# Interface.net
KiCad netlist of a schematic drawn in Altium Designer
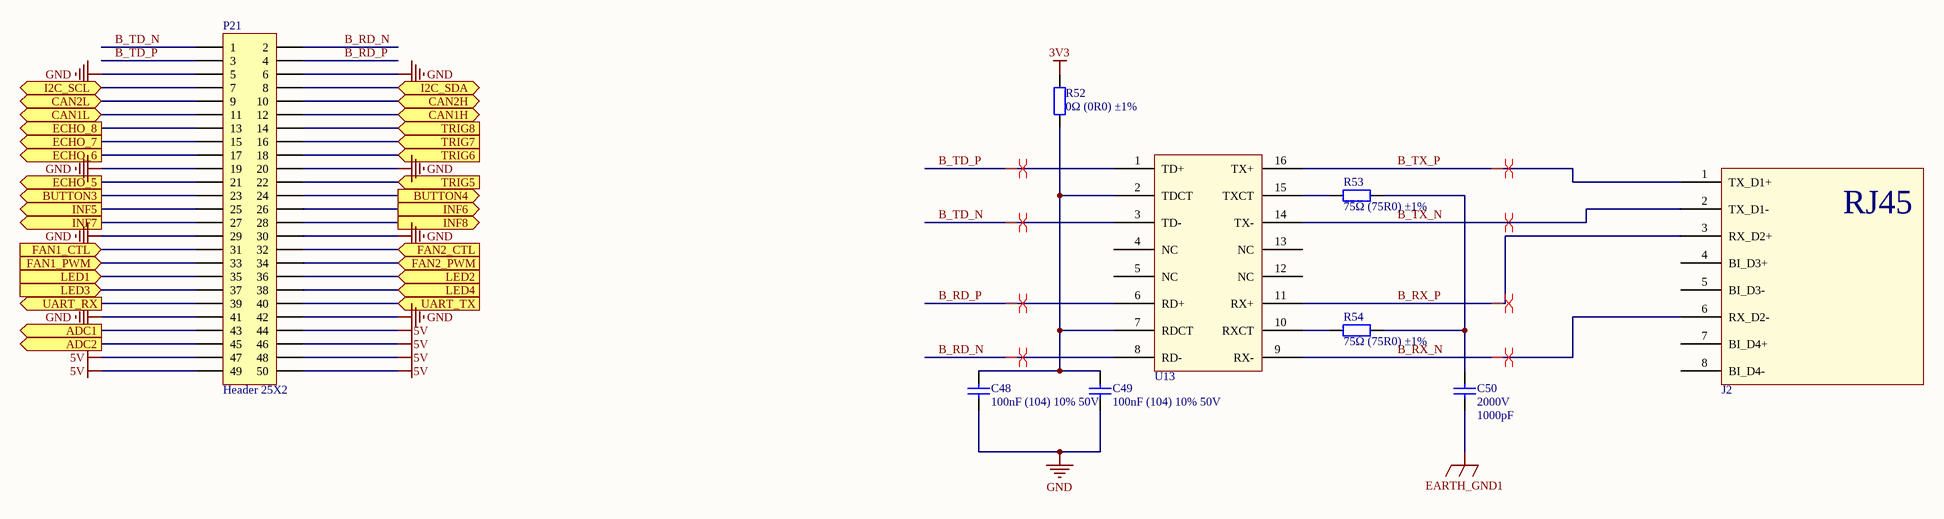
[diagram p0: Interface.SchDoc]

(export (version "E")
  (design (tool "Eeschema 10.0.6"))
  (components
    (comp (ref "C48")
      (value "100nF (104) 10% 50V")
      (footprint "0603_C")
      (description "贴片电容")
      (libsource (lib "Miscellaneous Devices LC") (part "0603 100nF (104) 10% 50V"))
    )
    (comp (ref "C49")
      (value "100nF (104) 10% 50V")
      (footprint "0603_C")
      (description "贴片电容")
      (libsource (lib "Miscellaneous Devices LC") (part "0603 100nF (104) 10% 50V"))
    )
    (comp (ref "C50")
      (value "2000V")
      (footprint "CAP1210N")
      (description "CAP 1000pF ±10% 2000V (2kV) Ceramic Capacitor X7R 1210 (3225 Metric)")
      (fields
        (field (name "ALTIUM_VALUE") "1000pF")
        (field (name "MANUFACTURER") "Samsung Electro-Mechanics")
        (field (name "MANUFACTURER PART NUMBER") "CL32B102KJFNNNE")
      )
      (libsource (lib "RoboteX") (part "Cap Non-Polar"))
    )
    (comp (ref "J2")
      (value "Jack Modular Connector 8p8c (RJ45, Ethernet) Vertical Unshielded Cat3")
      (footprint "RJ45-5556416-1")
      (description "RJ45 connector 180 degrees")
      (fields (field (name "PART NUMBER") "5556416-1") (field (name "MANUFACTURER") "TE"))
      (libsource (lib "RoboteX") (part "RJ45_180"))
    )
    (comp (ref "P21")
      (value "Header 25X2")
      (footprint "HDR_2X25")
      (description "Header, 25-Pin, Dual row")
      (fields (field (name "PUBLISHER") "Altium Limited"))
      (libsource (lib "Miscellaneous Connectors") (part "Header 25X2"))
    )
    (comp (ref "R52")
      (value "0Ω (0R0) ±1%")
      (footprint "0603_R")
      (description "贴片电阻")
      (libsource (lib "Miscellaneous Devices LC") (part "0603 0Ω (0R0) 1%"))
    )
    (comp (ref "R53")
      (value "75Ω (75R0) ±1%")
      (footprint "0603_R")
      (description "贴片电阻")
      (libsource (lib "Miscellaneous Devices LC") (part "0603 75Ω (75R0) 1%"))
    )
    (comp (ref "R54")
      (value "75Ω (75R0) ±1%")
      (footprint "0603_R")
      (description "贴片电阻")
      (libsource (lib "Miscellaneous Devices LC") (part "0603 75Ω (75R0) 1%"))
    )
    (comp (ref "U13")
      (value "TRANSFORMER")
      (footprint "Bel_transformer")
      (description "MODULE XFRMR LAN 10/100B-TX SMD")
      (fields
        (field (name "MANUFACTURER") "Bel Fuse Inc.")
        (field (name "MANUFACTURER PART NUMBER") "S558-5999-U7-F")
      )
      (libsource (lib "RoboteX") (part "Transformer"))
    )
  )
  (nets
    (net (code "1") (name "/ADC1") (class "Default")
      (node (ref "P21") (pin "43") (pinfunction "43_43") (pintype "passive"))
    )
    (net (code "2") (name "/ADC2") (class "Default")
      (node (ref "P21") (pin "45") (pinfunction "45_45") (pintype "passive"))
    )
    (net (code "3") (name "/BUTTON3") (class "Default")
      (node (ref "P21") (pin "23") (pinfunction "23_23") (pintype "passive"))
    )
    (net (code "4") (name "/BUTTON4") (class "Default")
      (node (ref "P21") (pin "24") (pinfunction "24_24") (pintype "passive"))
    )
    (net (code "5") (name "/B_RD_N") (class "Default")
      (node (ref "P21") (pin "2") (pinfunction "2_2") (pintype "passive"))
      (node (ref "U13") (pin "8") (pinfunction "RD-_8") (pintype "passive"))
    )
    (net (code "6") (name "/B_RD_P") (class "Default")
      (node (ref "P21") (pin "4") (pinfunction "4_4") (pintype "passive"))
      (node (ref "U13") (pin "6") (pinfunction "RD+_6") (pintype "passive"))
    )
    (net (code "7") (name "/B_RX_N") (class "Default")
      (node (ref "J2") (pin "6") (pinfunction "RX_D2-_6") (pintype "passive"))
      (node (ref "U13") (pin "9") (pinfunction "RX-_9") (pintype "passive"))
    )
    (net (code "8") (name "/B_RX_P") (class "Default")
      (node (ref "J2") (pin "3") (pinfunction "RX_D2+_3") (pintype "passive"))
      (node (ref "U13") (pin "11") (pinfunction "RX+_11") (pintype "passive"))
    )
    (net (code "9") (name "/B_TD_N") (class "Default")
      (node (ref "P21") (pin "1") (pinfunction "1_1") (pintype "passive"))
      (node (ref "U13") (pin "3") (pinfunction "TD-_3") (pintype "passive"))
    )
    (net (code "10") (name "/B_TD_P") (class "Default")
      (node (ref "P21") (pin "3") (pinfunction "3_3") (pintype "passive"))
      (node (ref "U13") (pin "1") (pinfunction "TD+_1") (pintype "passive"))
    )
    (net (code "11") (name "/B_TX_N") (class "Default")
      (node (ref "J2") (pin "2") (pinfunction "TX_D1-_2") (pintype "passive"))
      (node (ref "U13") (pin "14") (pinfunction "TX-_14") (pintype "passive"))
    )
    (net (code "12") (name "/B_TX_P") (class "Default")
      (node (ref "J2") (pin "1") (pinfunction "TX_D1+_1") (pintype "passive"))
      (node (ref "U13") (pin "16") (pinfunction "TX+_16") (pintype "passive"))
    )
    (net (code "13") (name "/CAN1H") (class "Default")
      (node (ref "P21") (pin "12") (pinfunction "12_12") (pintype "passive"))
    )
    (net (code "14") (name "/CAN1L") (class "Default")
      (node (ref "P21") (pin "11") (pinfunction "11_11") (pintype "passive"))
    )
    (net (code "15") (name "/CAN2H") (class "Default")
      (node (ref "P21") (pin "10") (pinfunction "10_10") (pintype "passive"))
    )
    (net (code "16") (name "/CAN2L") (class "Default")
      (node (ref "P21") (pin "9") (pinfunction "9_9") (pintype "passive"))
    )
    (net (code "17") (name "/ECHO_5") (class "Default")
      (node (ref "P21") (pin "21") (pinfunction "21_21") (pintype "passive"))
    )
    (net (code "18") (name "/ECHO_6") (class "Default")
      (node (ref "P21") (pin "17") (pinfunction "17_17") (pintype "passive"))
    )
    (net (code "19") (name "/ECHO_7") (class "Default")
      (node (ref "P21") (pin "15") (pinfunction "15_15") (pintype "passive"))
    )
    (net (code "20") (name "/ECHO_8") (class "Default")
      (node (ref "P21") (pin "13") (pinfunction "13_13") (pintype "passive"))
    )
    (net (code "21") (name "/FAN1_CTL") (class "Default")
      (node (ref "P21") (pin "31") (pinfunction "31_31") (pintype "passive"))
    )
    (net (code "22") (name "/FAN1_PWM") (class "Default")
      (node (ref "P21") (pin "33") (pinfunction "33_33") (pintype "passive"))
    )
    (net (code "23") (name "/FAN2_CTL") (class "Default")
      (node (ref "P21") (pin "32") (pinfunction "32_32") (pintype "passive"))
    )
    (net (code "24") (name "/FAN2_PWM") (class "Default")
      (node (ref "P21") (pin "34") (pinfunction "34_34") (pintype "passive"))
    )
    (net (code "25") (name "/I2C_SCL") (class "Default")
      (node (ref "P21") (pin "7") (pinfunction "7_7") (pintype "passive"))
    )
    (net (code "26") (name "/I2C_SDA") (class "Default")
      (node (ref "P21") (pin "8") (pinfunction "8_8") (pintype "passive"))
    )
    (net (code "27") (name "/INF5") (class "Default")
      (node (ref "P21") (pin "25") (pinfunction "25_25") (pintype "passive"))
    )
    (net (code "28") (name "/INF6") (class "Default")
      (node (ref "P21") (pin "26") (pinfunction "26_26") (pintype "passive"))
    )
    (net (code "29") (name "/INF7") (class "Default")
      (node (ref "P21") (pin "27") (pinfunction "27_27") (pintype "passive"))
    )
    (net (code "30") (name "/INF8") (class "Default")
      (node (ref "P21") (pin "28") (pinfunction "28_28") (pintype "passive"))
    )
    (net (code "31") (name "/LED1") (class "Default")
      (node (ref "P21") (pin "35") (pinfunction "35_35") (pintype "passive"))
    )
    (net (code "32") (name "/LED2") (class "Default")
      (node (ref "P21") (pin "36") (pinfunction "36_36") (pintype "passive"))
    )
    (net (code "33") (name "/LED3") (class "Default")
      (node (ref "P21") (pin "37") (pinfunction "37_37") (pintype "passive"))
    )
    (net (code "34") (name "/LED4") (class "Default")
      (node (ref "P21") (pin "38") (pinfunction "38_38") (pintype "passive"))
    )
    (net (code "35") (name "/TRIG5") (class "Default")
      (node (ref "P21") (pin "22") (pinfunction "22_22") (pintype "passive"))
    )
    (net (code "36") (name "/TRIG6") (class "Default")
      (node (ref "P21") (pin "18") (pinfunction "18_18") (pintype "passive"))
    )
    (net (code "37") (name "/TRIG7") (class "Default")
      (node (ref "P21") (pin "16") (pinfunction "16_16") (pintype "passive"))
    )
    (net (code "38") (name "/TRIG8") (class "Default")
      (node (ref "P21") (pin "14") (pinfunction "14_14") (pintype "passive"))
    )
    (net (code "39") (name "/UART_RX") (class "Default")
      (node (ref "P21") (pin "39") (pinfunction "39_39") (pintype "passive"))
    )
    (net (code "40") (name "/UART_TX") (class "Default")
      (node (ref "P21") (pin "40") (pinfunction "40_40") (pintype "passive"))
    )
    (net (code "41") (name "3V3") (class "Default")
      (node (ref "R52") (pin "2") (pinfunction "2_2") (pintype "passive"))
    )
    (net (code "42") (name "5V") (class "Default")
      (node (ref "P21") (pin "44") (pinfunction "44_44") (pintype "passive"))
      (node (ref "P21") (pin "46") (pinfunction "46_46") (pintype "passive"))
      (node (ref "P21") (pin "47") (pinfunction "47_47") (pintype "passive"))
      (node (ref "P21") (pin "48") (pinfunction "48_48") (pintype "passive"))
      (node (ref "P21") (pin "49") (pinfunction "49_49") (pintype "passive"))
      (node (ref "P21") (pin "50") (pinfunction "50_50") (pintype "passive"))
    )
    (net (code "43") (name "EARTH_GND1") (class "Default")
      (node (ref "C50") (pin "1") (pinfunction "1_1") (pintype "passive"))
    )
    (net (code "44") (name "GND") (class "Default")
      (node (ref "C48") (pin "2") (pinfunction "2_2") (pintype "passive"))
      (node (ref "C49") (pin "1") (pinfunction "1_1") (pintype "passive"))
      (node (ref "P21") (pin "19") (pinfunction "19_19") (pintype "passive"))
      (node (ref "P21") (pin "20") (pinfunction "20_20") (pintype "passive"))
      (node (ref "P21") (pin "29") (pinfunction "29_29") (pintype "passive"))
      (node (ref "P21") (pin "30") (pinfunction "30_30") (pintype "passive"))
      (node (ref "P21") (pin "41") (pinfunction "41_41") (pintype "passive"))
      (node (ref "P21") (pin "42") (pinfunction "42_42") (pintype "passive"))
      (node (ref "P21") (pin "5") (pinfunction "5_5") (pintype "passive"))
      (node (ref "P21") (pin "6") (pinfunction "6_6") (pintype "passive"))
    )
    (net (code "45") (name "Net-(C50-Pad2)") (class "Default")
      (node (ref "C50") (pin "2") (pinfunction "2_2") (pintype "passive"))
      (node (ref "R53") (pin "2") (pinfunction "2_2") (pintype "passive"))
      (node (ref "R54") (pin "2") (pinfunction "2_2") (pintype "passive"))
    )
    (net (code "46") (name "Net-(U13-RDCT)") (class "Default")
      (node (ref "C48") (pin "1") (pinfunction "1_1") (pintype "passive"))
      (node (ref "C49") (pin "2") (pinfunction "2_2") (pintype "passive"))
      (node (ref "R52") (pin "1") (pinfunction "1_1") (pintype "passive"))
      (node (ref "U13") (pin "2") (pinfunction "TDCT_2") (pintype "passive"))
      (node (ref "U13") (pin "7") (pinfunction "RDCT_7") (pintype "passive"))
    )
    (net (code "47") (name "Net-(U13-RXCT)") (class "Default")
      (node (ref "R54") (pin "1") (pinfunction "1_1") (pintype "passive"))
      (node (ref "U13") (pin "10") (pinfunction "RXCT_10") (pintype "passive"))
    )
    (net (code "48") (name "Net-(U13-TXCT)") (class "Default")
      (node (ref "R53") (pin "1") (pinfunction "1_1") (pintype "passive"))
      (node (ref "U13") (pin "15") (pinfunction "TXCT_15") (pintype "passive"))
    )
    (net (code "49") (name "unconnected-(J2-BI_D3+-Pad4)") (class "Default")
      (node (ref "J2") (pin "4") (pinfunction "BI_D3+_4") (pintype "passive"))
    )
    (net (code "50") (name "unconnected-(J2-BI_D3--Pad5)") (class "Default")
      (node (ref "J2") (pin "5") (pinfunction "BI_D3-_5") (pintype "passive"))
    )
    (net (code "51") (name "unconnected-(J2-BI_D4+-Pad7)") (class "Default")
      (node (ref "J2") (pin "7") (pinfunction "BI_D4+_7") (pintype "passive"))
    )
    (net (code "52") (name "unconnected-(J2-BI_D4--Pad8)") (class "Default")
      (node (ref "J2") (pin "8") (pinfunction "BI_D4-_8") (pintype "passive"))
    )
    (net (code "53") (name "unconnected-(U13-NC-Pad4)") (class "Default")
      (node (ref "U13") (pin "4") (pinfunction "NC_4") (pintype "passive"))
    )
    (net (code "54") (name "unconnected-(U13-NC-Pad5)") (class "Default")
      (node (ref "U13") (pin "5") (pinfunction "NC_5") (pintype "passive"))
    )
    (net (code "55") (name "unconnected-(U13-NC-Pad12)") (class "Default")
      (node (ref "U13") (pin "12") (pinfunction "NC_12") (pintype "passive"))
    )
    (net (code "56") (name "unconnected-(U13-NC-Pad13)") (class "Default")
      (node (ref "U13") (pin "13") (pinfunction "NC_13") (pintype "passive"))
    )
  )
)
